# Battery_Checker.net
KiCad netlist of a schematic drawn in EAGLE
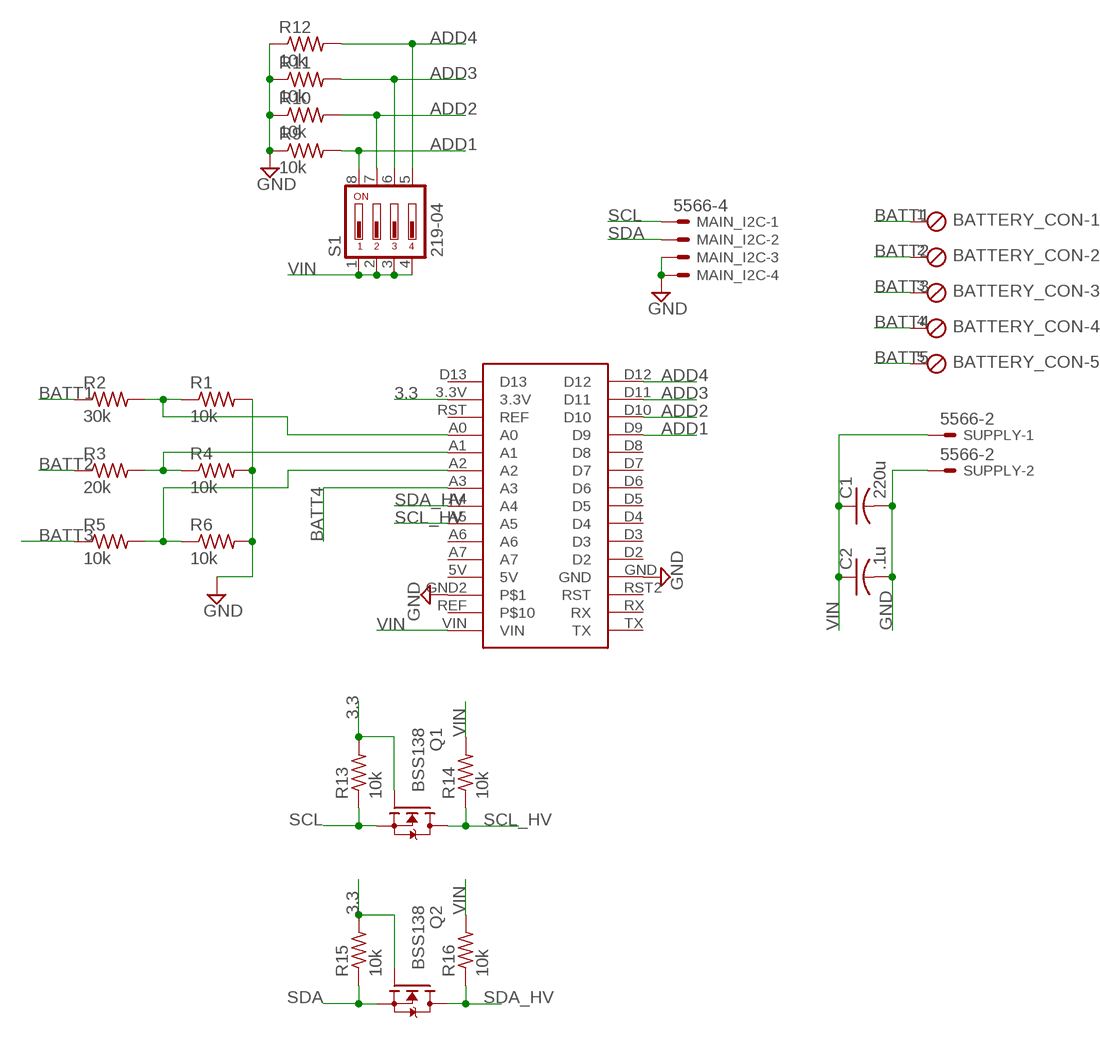
[diagram p0: schematic, sheet 1]

(export (version "E")
  (design (tool "Eeschema 10.0.6"))
  (components
    (comp (ref "BATTERY_CON")
      (value "MPT5")
      (footprint "eagle-import:5POL254")
      (libsource (lib "eagle-import") (part "MPT5"))
    )
    (comp (ref "C1")
      (value "220u")
      (footprint "eagle-import:C1206")
      (libsource (lib "eagle-import") (part "C-USC1206"))
    )
    (comp (ref "C2")
      (value ".1u")
      (footprint "eagle-import:C1206")
      (libsource (lib "eagle-import") (part "C-USC1206"))
    )
    (comp (ref "MAIN_I2C")
      (value "5566-4")
      (footprint "eagle-import:5566-4")
      (fields (field (name "MF") "MOLEX"))
      (libsource (lib "eagle-import") (part "5566-4"))
    )
    (comp (ref "Q1")
      (value "BSS138")
      (footprint "eagle-import:SOT23")
      (fields (field (name "MF") "Fairchild"))
      (libsource (lib "eagle-import") (part "BSS138"))
    )
    (comp (ref "Q2")
      (value "BSS138")
      (footprint "eagle-import:SOT23")
      (fields (field (name "MF") "Fairchild"))
      (libsource (lib "eagle-import") (part "BSS138"))
    )
    (comp (ref "R1")
      (value "10k")
      (footprint "eagle-import:R1206")
      (libsource (lib "eagle-import") (part "R-US_R1206"))
    )
    (comp (ref "R2")
      (value "30k")
      (footprint "eagle-import:R1206")
      (libsource (lib "eagle-import") (part "R-US_R1206"))
    )
    (comp (ref "R3")
      (value "20k")
      (footprint "eagle-import:R1206")
      (libsource (lib "eagle-import") (part "R-US_R1206"))
    )
    (comp (ref "R4")
      (value "10k")
      (footprint "eagle-import:R1206")
      (libsource (lib "eagle-import") (part "R-US_R1206"))
    )
    (comp (ref "R5")
      (value "10k")
      (footprint "eagle-import:R1206")
      (libsource (lib "eagle-import") (part "R-US_R1206"))
    )
    (comp (ref "R6")
      (value "10k")
      (footprint "eagle-import:R1206")
      (libsource (lib "eagle-import") (part "R-US_R1206"))
    )
    (comp (ref "R9")
      (value "10k")
      (footprint "eagle-import:R1206")
      (libsource (lib "eagle-import") (part "R-US_R1206"))
    )
    (comp (ref "R10")
      (value "10k")
      (footprint "eagle-import:R1206")
      (libsource (lib "eagle-import") (part "R-US_R1206"))
    )
    (comp (ref "R11")
      (value "10k")
      (footprint "eagle-import:R1206")
      (libsource (lib "eagle-import") (part "R-US_R1206"))
    )
    (comp (ref "R12")
      (value "10k")
      (footprint "eagle-import:R1206")
      (libsource (lib "eagle-import") (part "R-US_R1206"))
    )
    (comp (ref "R13")
      (value "10k")
      (footprint "eagle-import:R1206")
      (libsource (lib "eagle-import") (part "R-US_R1206"))
    )
    (comp (ref "R14")
      (value "10k")
      (footprint "eagle-import:R1206")
      (libsource (lib "eagle-import") (part "R-US_R1206"))
    )
    (comp (ref "R15")
      (value "10k")
      (footprint "eagle-import:R1206")
      (libsource (lib "eagle-import") (part "R-US_R1206"))
    )
    (comp (ref "R16")
      (value "10k")
      (footprint "eagle-import:R1206")
      (libsource (lib "eagle-import") (part "R-US_R1206"))
    )
    (comp (ref "S1")
      (value "219-04")
      (footprint "eagle-import:CTS-219-04")
      (libsource (lib "eagle-import") (part "219-04"))
    )
    (comp (ref "SUPPLY")
      (value "5566-2")
      (footprint "eagle-import:5566-2")
      (fields (field (name "MF") "MOLEX"))
      (libsource (lib "eagle-import") (part "5566-2"))
    )
    (comp (ref "U$1")
      (value "ARDUINO_NANO")
      (footprint "eagle-import:ADUINO_NANO")
      (libsource (lib "eagle-import") (part "ARDUINO_NANO"))
    )
  )
  (nets
    (net (code "1") (name "/3.3") (class "Default")
      (node (ref "Q1") (pin "1") (pinfunction "G_1") (pintype "passive"))
      (node (ref "Q2") (pin "1") (pinfunction "G_1") (pintype "passive"))
      (node (ref "R13") (pin "2") (pinfunction "2_2") (pintype "passive"))
      (node (ref "R15") (pin "2") (pinfunction "2_2") (pintype "passive"))
      (node (ref "U$1") (pin "3.3V") (pinfunction "3.3V_3.3V") (pintype "power_in"))
    )
    (net (code "2") (name "/5V") (class "Default")
      (node (ref "U$1") (pin "5V") (pinfunction "5V_5V") (pintype "power_in"))
    )
    (net (code "3") (name "/ADD1") (class "Default")
      (node (ref "R9") (pin "2") (pinfunction "2_2") (pintype "passive"))
      (node (ref "S1") (pin "8") (pinfunction "8_8") (pintype "passive"))
      (node (ref "U$1") (pin "D9") (pinfunction "D9_D9") (pintype "bidirectional"))
    )
    (net (code "4") (name "/ADD2") (class "Default")
      (node (ref "R10") (pin "2") (pinfunction "2_2") (pintype "passive"))
      (node (ref "S1") (pin "7") (pinfunction "7_7") (pintype "passive"))
      (node (ref "U$1") (pin "D10") (pinfunction "D10_D10") (pintype "bidirectional"))
    )
    (net (code "5") (name "/ADD3") (class "Default")
      (node (ref "R11") (pin "2") (pinfunction "2_2") (pintype "passive"))
      (node (ref "S1") (pin "6") (pinfunction "6_6") (pintype "passive"))
      (node (ref "U$1") (pin "D11") (pinfunction "D11_D11") (pintype "bidirectional"))
    )
    (net (code "6") (name "/ADD4") (class "Default")
      (node (ref "R12") (pin "2") (pinfunction "2_2") (pintype "passive"))
      (node (ref "S1") (pin "5") (pinfunction "5_5") (pintype "passive"))
      (node (ref "U$1") (pin "D12") (pinfunction "D12_D12") (pintype "bidirectional"))
    )
    (net (code "7") (name "/BATT1") (class "Default")
      (node (ref "BATTERY_CON") (pin "1") (pinfunction "1_1") (pintype "passive"))
      (node (ref "R2") (pin "1") (pinfunction "1_1") (pintype "passive"))
    )
    (net (code "8") (name "/BATT2") (class "Default")
      (node (ref "BATTERY_CON") (pin "2") (pinfunction "1_2") (pintype "passive"))
      (node (ref "R3") (pin "1") (pinfunction "1_1") (pintype "passive"))
    )
    (net (code "9") (name "/BATT3") (class "Default")
      (node (ref "BATTERY_CON") (pin "3") (pinfunction "1_3") (pintype "passive"))
      (node (ref "R5") (pin "1") (pinfunction "1_1") (pintype "passive"))
    )
    (net (code "10") (name "/BATT4") (class "Default")
      (node (ref "BATTERY_CON") (pin "4") (pinfunction "1_4") (pintype "passive"))
      (node (ref "U$1") (pin "A3") (pinfunction "A3_A3") (pintype "input"))
    )
    (net (code "11") (name "/BATT5") (class "Default")
      (node (ref "BATTERY_CON") (pin "5") (pinfunction "1_5") (pintype "passive"))
    )
    (net (code "12") (name "/P$10") (class "Default")
      (node (ref "U$1") (pin "REF") (pinfunction "P$10_REF") (pintype "power_in"))
    )
    (net (code "13") (name "/SCL") (class "Default")
      (node (ref "MAIN_I2C") (pin "1") (pinfunction "S_1") (pintype "passive"))
      (node (ref "Q1") (pin "2") (pinfunction "S_2") (pintype "passive"))
      (node (ref "R13") (pin "1") (pinfunction "1_1") (pintype "passive"))
    )
    (net (code "14") (name "/SCL_HV") (class "Default")
      (node (ref "Q1") (pin "3") (pinfunction "D_3") (pintype "passive"))
      (node (ref "R14") (pin "1") (pinfunction "1_1") (pintype "passive"))
      (node (ref "U$1") (pin "A5") (pinfunction "A5_A5") (pintype "input"))
    )
    (net (code "15") (name "/SDA") (class "Default")
      (node (ref "MAIN_I2C") (pin "2") (pinfunction "S_2") (pintype "passive"))
      (node (ref "Q2") (pin "2") (pinfunction "S_2") (pintype "passive"))
      (node (ref "R15") (pin "1") (pinfunction "1_1") (pintype "passive"))
    )
    (net (code "16") (name "/SDA_HV") (class "Default")
      (node (ref "Q2") (pin "3") (pinfunction "D_3") (pintype "passive"))
      (node (ref "R16") (pin "1") (pinfunction "1_1") (pintype "passive"))
      (node (ref "U$1") (pin "A4") (pinfunction "A4_A4") (pintype "input"))
    )
    (net (code "17") (name "/VIN") (class "Default")
      (node (ref "C1") (pin "1") (pinfunction "1_1") (pintype "passive"))
      (node (ref "C2") (pin "1") (pinfunction "1_1") (pintype "passive"))
      (node (ref "R14") (pin "2") (pinfunction "2_2") (pintype "passive"))
      (node (ref "R16") (pin "2") (pinfunction "2_2") (pintype "passive"))
      (node (ref "S1") (pin "1") (pinfunction "1_1") (pintype "passive"))
      (node (ref "S1") (pin "2") (pinfunction "2_2") (pintype "passive"))
      (node (ref "S1") (pin "3") (pinfunction "3_3") (pintype "passive"))
      (node (ref "S1") (pin "4") (pinfunction "4_4") (pintype "passive"))
      (node (ref "SUPPLY") (pin "1") (pinfunction "S_1") (pintype "passive"))
      (node (ref "U$1") (pin "VIN") (pinfunction "VIN_VIN") (pintype "power_in"))
    )
    (net (code "18") (name "GND") (class "Default")
      (node (ref "C1") (pin "2") (pinfunction "2_2") (pintype "passive"))
      (node (ref "C2") (pin "2") (pinfunction "2_2") (pintype "passive"))
      (node (ref "MAIN_I2C") (pin "3") (pinfunction "S_3") (pintype "passive"))
      (node (ref "MAIN_I2C") (pin "4") (pinfunction "S_4") (pintype "passive"))
      (node (ref "R1") (pin "2") (pinfunction "2_2") (pintype "passive"))
      (node (ref "R10") (pin "1") (pinfunction "1_1") (pintype "passive"))
      (node (ref "R11") (pin "1") (pinfunction "1_1") (pintype "passive"))
      (node (ref "R12") (pin "1") (pinfunction "1_1") (pintype "passive"))
      (node (ref "R4") (pin "2") (pinfunction "2_2") (pintype "passive"))
      (node (ref "R6") (pin "2") (pinfunction "2_2") (pintype "passive"))
      (node (ref "R9") (pin "1") (pinfunction "1_1") (pintype "passive"))
      (node (ref "SUPPLY") (pin "2") (pinfunction "S_2") (pintype "passive"))
      (node (ref "U$1") (pin "GND") (pinfunction "GND_GND") (pintype "power_in"))
      (node (ref "U$1") (pin "GND2") (pinfunction "P$1_GND2") (pintype "input"))
    )
    (net (code "19") (name "Net-(R1-Pad1)") (class "Default")
      (node (ref "R1") (pin "1") (pinfunction "1_1") (pintype "passive"))
      (node (ref "R2") (pin "2") (pinfunction "2_2") (pintype "passive"))
      (node (ref "U$1") (pin "A0") (pinfunction "A0_A0") (pintype "input"))
    )
    (net (code "20") (name "Net-(R3-Pad2)") (class "Default")
      (node (ref "R3") (pin "2") (pinfunction "2_2") (pintype "passive"))
      (node (ref "R4") (pin "1") (pinfunction "1_1") (pintype "passive"))
      (node (ref "U$1") (pin "A1") (pinfunction "A1_A1") (pintype "input"))
    )
    (net (code "21") (name "Net-(R5-Pad2)") (class "Default")
      (node (ref "R5") (pin "2") (pinfunction "2_2") (pintype "passive"))
      (node (ref "R6") (pin "1") (pinfunction "1_1") (pintype "passive"))
      (node (ref "U$1") (pin "A2") (pinfunction "A2_A2") (pintype "input"))
    )
    (net (code "22") (name "unconnected-(U$1-PadA6)") (class "Default")
      (node (ref "U$1") (pin "A6") (pinfunction "A6_A6") (pintype "input"))
    )
    (net (code "23") (name "unconnected-(U$1-PadA7)") (class "Default")
      (node (ref "U$1") (pin "A7") (pinfunction "A7_A7") (pintype "input"))
    )
    (net (code "24") (name "unconnected-(U$1-PadD2)") (class "Default")
      (node (ref "U$1") (pin "D2") (pinfunction "D2_D2") (pintype "bidirectional"))
    )
    (net (code "25") (name "unconnected-(U$1-PadD3)") (class "Default")
      (node (ref "U$1") (pin "D3") (pinfunction "D3_D3") (pintype "bidirectional"))
    )
    (net (code "26") (name "unconnected-(U$1-PadD4)") (class "Default")
      (node (ref "U$1") (pin "D4") (pinfunction "D4_D4") (pintype "bidirectional"))
    )
    (net (code "27") (name "unconnected-(U$1-PadD5)") (class "Default")
      (node (ref "U$1") (pin "D5") (pinfunction "D5_D5") (pintype "bidirectional"))
    )
    (net (code "28") (name "unconnected-(U$1-PadD6)") (class "Default")
      (node (ref "U$1") (pin "D6") (pinfunction "D6_D6") (pintype "bidirectional"))
    )
    (net (code "29") (name "unconnected-(U$1-PadD7)") (class "Default")
      (node (ref "U$1") (pin "D7") (pinfunction "D7_D7") (pintype "bidirectional"))
    )
    (net (code "30") (name "unconnected-(U$1-PadD8)") (class "Default")
      (node (ref "U$1") (pin "D8") (pinfunction "D8_D8") (pintype "bidirectional"))
    )
    (net (code "31") (name "unconnected-(U$1-PadD13)") (class "Default")
      (node (ref "U$1") (pin "D13") (pinfunction "D13_D13") (pintype "bidirectional"))
    )
    (net (code "32") (name "unconnected-(U$1-PadRX)") (class "Default")
      (node (ref "U$1") (pin "RX") (pinfunction "RX_RX") (pintype "bidirectional"))
    )
    (net (code "33") (name "unconnected-(U$1-PadTX)") (class "Default")
      (node (ref "U$1") (pin "TX") (pinfunction "TX_TX") (pintype "bidirectional"))
    )
    (net (code "34") (name "unconnected-(U$1-REF-PadRST)") (class "Default")
      (node (ref "U$1") (pin "RST") (pinfunction "REF_RST") (pintype "input"))
    )
    (net (code "35") (name "unconnected-(U$1-RST-PadRST2)") (class "Default")
      (node (ref "U$1") (pin "RST2") (pinfunction "RST_RST2") (pintype "input"))
    )
  )
)
